# T2BasicSerialSplitterRevC.net
KiCad netlist of a schematic drawn in EAGLE
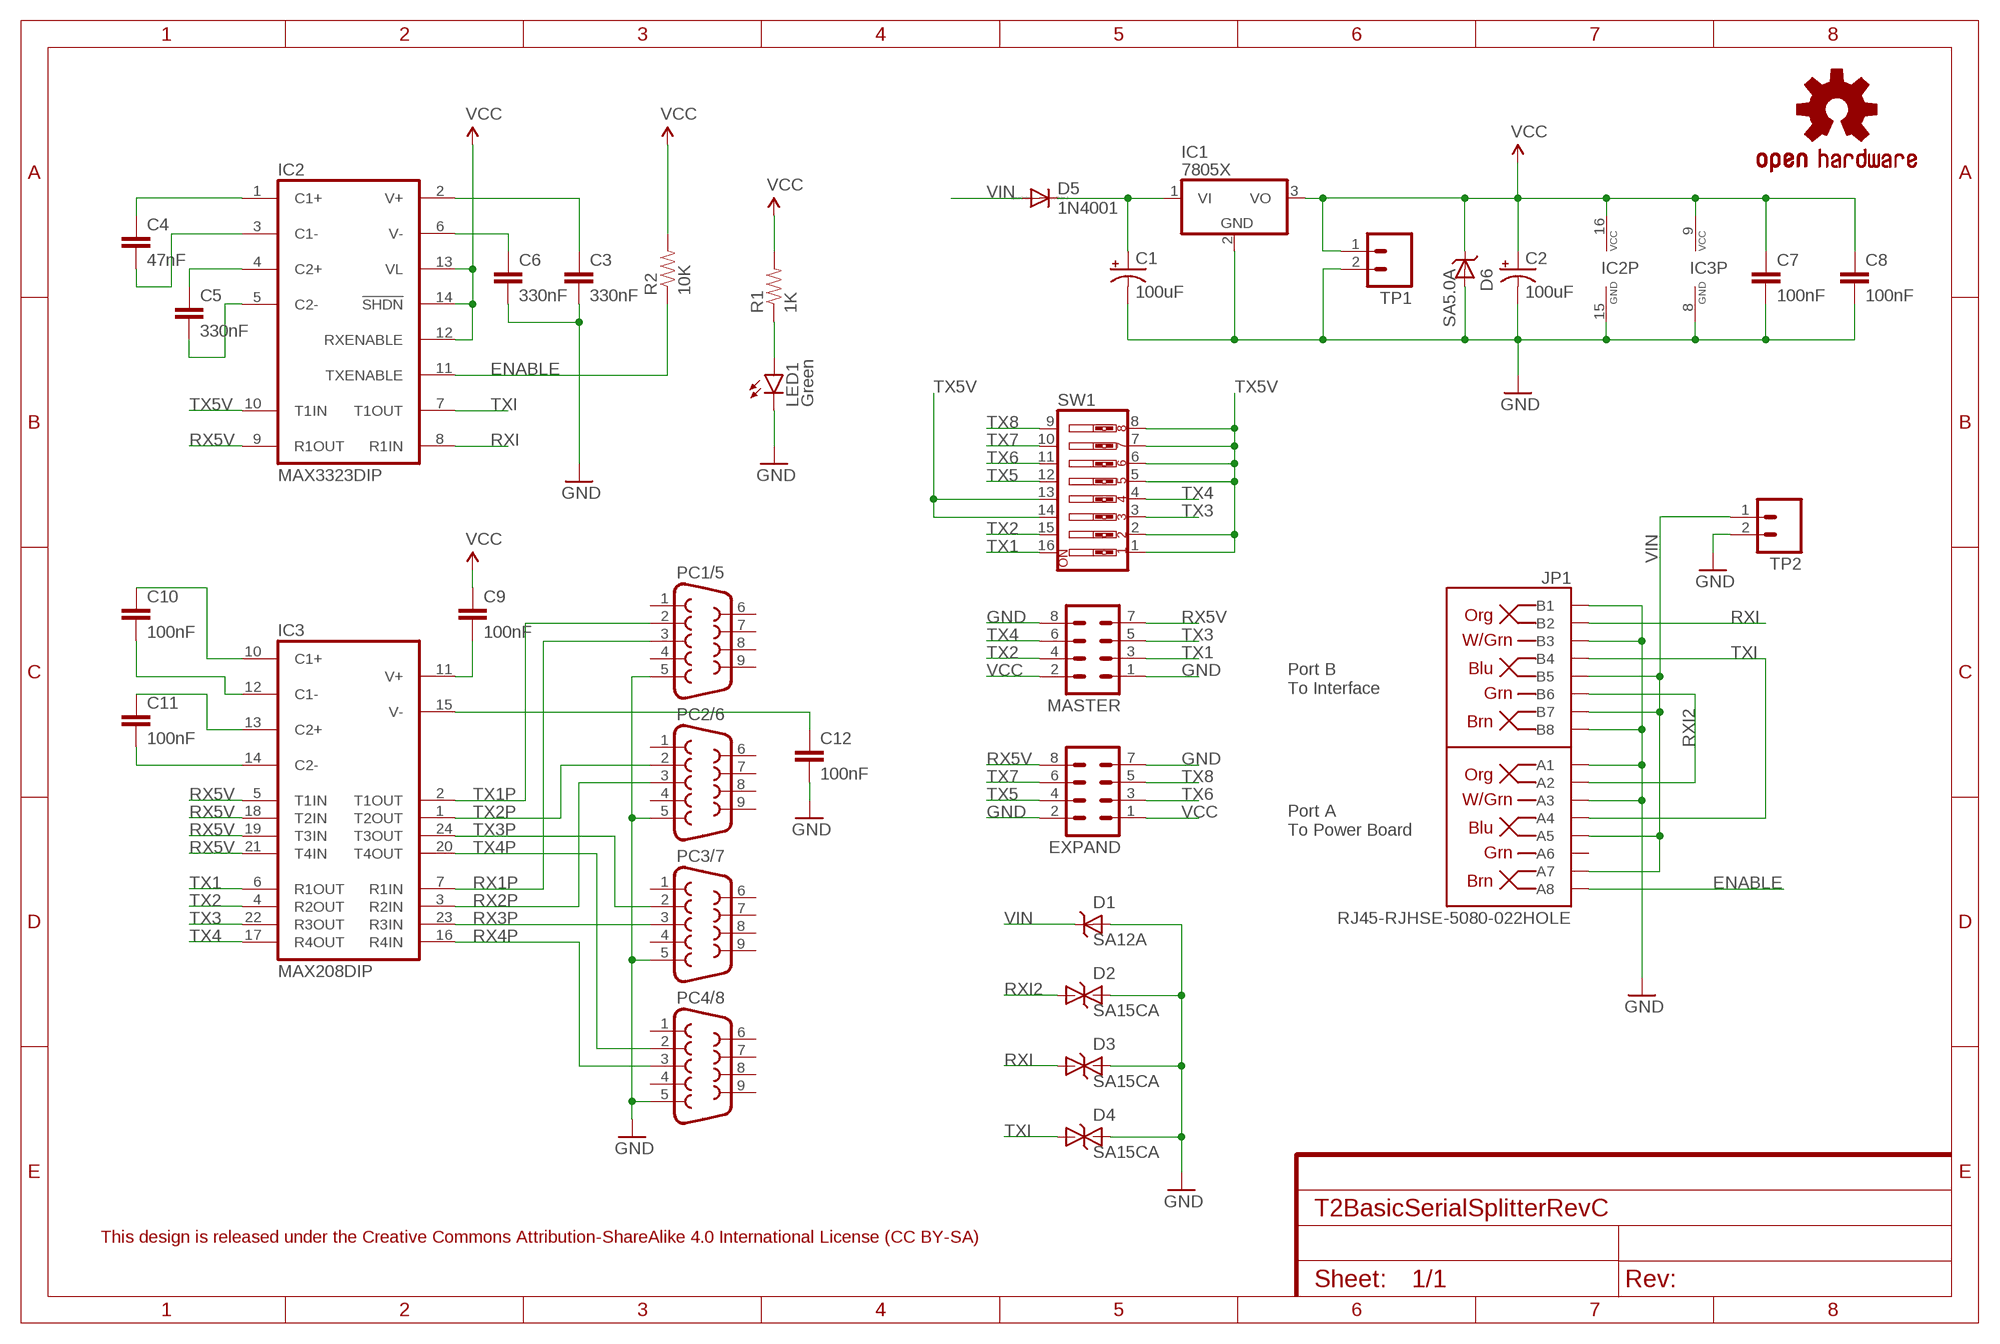
[diagram p0: schematic, sheet 1]

(export (version "E")
  (design (tool "Eeschema 10.0.6"))
  (components
    (comp (ref "C1")
      (value "100uF")
      (footprint "eagle-import:CPOL-RADIAL-100UF-25V")
      (libsource (lib "eagle-import") (part "CAP_POLPTH1"))
    )
    (comp (ref "C2")
      (value "100uF")
      (footprint "eagle-import:CPOL-RADIAL-100UF-25V")
      (libsource (lib "eagle-import") (part "CAP_POLPTH1"))
    )
    (comp (ref "C3")
      (value "330nF")
      (footprint "eagle-import:CAP-PTH-SMALL")
      (libsource (lib "eagle-import") (part "CAPPTH"))
    )
    (comp (ref "C4")
      (value "47nF")
      (footprint "eagle-import:CAP-PTH-SMALL")
      (libsource (lib "eagle-import") (part "CAPPTH"))
    )
    (comp (ref "C5")
      (value "330nF")
      (footprint "eagle-import:CAP-PTH-SMALL")
      (libsource (lib "eagle-import") (part "CAPPTH"))
    )
    (comp (ref "C6")
      (value "330nF")
      (footprint "eagle-import:CAP-PTH-SMALL")
      (libsource (lib "eagle-import") (part "CAPPTH"))
    )
    (comp (ref "C7")
      (value "100nF")
      (footprint "eagle-import:CAP-PTH-SMALL")
      (libsource (lib "eagle-import") (part "CAPPTH"))
    )
    (comp (ref "C8")
      (value "100nF")
      (footprint "eagle-import:CAP-PTH-SMALL")
      (libsource (lib "eagle-import") (part "CAPPTH"))
    )
    (comp (ref "C9")
      (value "100nF")
      (footprint "eagle-import:CAP-PTH-SMALL")
      (libsource (lib "eagle-import") (part "CAPPTH"))
    )
    (comp (ref "C10")
      (value "100nF")
      (footprint "eagle-import:CAP-PTH-SMALL")
      (libsource (lib "eagle-import") (part "CAPPTH"))
    )
    (comp (ref "C11")
      (value "100nF")
      (footprint "eagle-import:CAP-PTH-SMALL")
      (libsource (lib "eagle-import") (part "CAPPTH"))
    )
    (comp (ref "C12")
      (value "100nF")
      (footprint "eagle-import:CAP-PTH-SMALL")
      (libsource (lib "eagle-import") (part "CAPPTH"))
    )
    (comp (ref "D1")
      (value "SA12A")
      (footprint "eagle-import:DO41_TVS_UNI")
      (libsource (lib "eagle-import") (part "SA12A"))
    )
    (comp (ref "D2")
      (value "SA15CA")
      (footprint "eagle-import:DO41_TVS_BI")
      (libsource (lib "eagle-import") (part "SA15CA"))
    )
    (comp (ref "D3")
      (value "SA15CA")
      (footprint "eagle-import:DO41_TVS_BI")
      (libsource (lib "eagle-import") (part "SA15CA"))
    )
    (comp (ref "D4")
      (value "SA15CA")
      (footprint "eagle-import:DO41_TVS_BI")
      (libsource (lib "eagle-import") (part "SA15CA"))
    )
    (comp (ref "D5")
      (value "1N4001")
      (footprint "eagle-import:DO41_DIODE")
      (libsource (lib "eagle-import") (part "1N4001"))
    )
    (comp (ref "D6")
      (value "SA5.0A")
      (footprint "eagle-import:DO41_TVS_UNI")
      (libsource (lib "eagle-import") (part "SA5.0A"))
    )
    (comp (ref "EXPAND")
      (value "M04X2POL")
      (footprint "eagle-import:2X4-POLARISED")
      (libsource (lib "eagle-import") (part "M04X2POL"))
    )
    (comp (ref "IC1")
      (value "7805X")
      (footprint "eagle-import:TO220H")
      (libsource (lib "eagle-import") (part "7805X"))
    )
    (comp (ref "IC2")
      (value "MAX3323DIP")
      (footprint "eagle-import:DIL16")
      (libsource (lib "eagle-import") (part "MAX3323DIP"))
    )
    (comp (ref "IC3")
      (value "MAX208DIP")
      (footprint "eagle-import:DIL24")
      (libsource (lib "eagle-import") (part "MAX208DIP"))
    )
    (comp (ref "JP1")
      (value "RJ45-RJHSE-5080-022HOLE")
      (footprint "eagle-import:RJ45-RJHSE-5080-02")
      (libsource (lib "eagle-import") (part "RJ45-RJHSE-5080-022HOLE"))
    )
    (comp (ref "LED1")
      (value "Green")
      (footprint "eagle-import:LED3MM_LARGEHOLES")
      (libsource (lib "eagle-import") (part "LED-LH3MM"))
    )
    (comp (ref "LOGO1")
      (value "OSHW-LOGOS")
      (footprint "eagle-import:OSHW-LOGO-S")
      (libsource (lib "eagle-import") (part "OSHW-LOGOS"))
    )
    (comp (ref "MASTER")
      (value "M04X2POL")
      (footprint "eagle-import:2X4-POLARISED")
      (libsource (lib "eagle-import") (part "M04X2POL"))
    )
    (comp (ref "PC1/5")
      (value "DB9-CONNECTOR-PCBFEMALE")
      (footprint "eagle-import:MULTICOMP-DB9-FEMALE-PCB-90DEG")
      (libsource (lib "eagle-import") (part "DB9-CONNECTOR-PCBFEMALE"))
    )
    (comp (ref "PC2/6")
      (value "DB9-CONNECTOR-PCBFEMALE")
      (footprint "eagle-import:MULTICOMP-DB9-FEMALE-PCB-90DEG")
      (libsource (lib "eagle-import") (part "DB9-CONNECTOR-PCBFEMALE"))
    )
    (comp (ref "PC3/7")
      (value "DB9-CONNECTOR-PCBFEMALE")
      (footprint "eagle-import:MULTICOMP-DB9-FEMALE-PCB-90DEG")
      (libsource (lib "eagle-import") (part "DB9-CONNECTOR-PCBFEMALE"))
    )
    (comp (ref "PC4/8")
      (value "DB9-CONNECTOR-PCBFEMALE")
      (footprint "eagle-import:MULTICOMP-DB9-FEMALE-PCB-90DEG")
      (libsource (lib "eagle-import") (part "DB9-CONNECTOR-PCBFEMALE"))
    )
    (comp (ref "R1")
      (value "1K")
      (footprint "eagle-import:AXIAL-0.4")
      (libsource (lib "eagle-import") (part "RESISTORPTH-1/4W"))
    )
    (comp (ref "R2")
      (value "10K")
      (footprint "eagle-import:AXIAL-0.4")
      (libsource (lib "eagle-import") (part "RESISTORPTH-1/4W"))
    )
    (comp (ref "SW1")
      (value "SW_DIP-8")
      (footprint "eagle-import:DIPSWITCH-08")
      (libsource (lib "eagle-import") (part "SW_DIP-8"))
    )
    (comp (ref "TP1")
      (value "M02PTH")
      (footprint "eagle-import:1X02")
      (libsource (lib "eagle-import") (part "M02PTH"))
    )
    (comp (ref "TP2")
      (value "M02PTH")
      (footprint "eagle-import:1X02")
      (libsource (lib "eagle-import") (part "M02PTH"))
    )
  )
  (nets
    (net (code "1") (name "/ENABLE") (class "Default")
      (node (ref "IC2") (pin "11") (pinfunction "TXENABLE_11") (pintype "bidirectional"))
      (node (ref "JP1") (pin "A8") (pinfunction "A8_A8") (pintype "bidirectional"))
      (node (ref "R2") (pin "P$1") (pinfunction "1_P$1") (pintype "passive"))
    )
    (net (code "2") (name "/RX1P") (class "Default")
      (node (ref "IC3") (pin "7") (pinfunction "R1IN_7") (pintype "input"))
      (node (ref "PC1/5") (pin "3") (pinfunction "3_3") (pintype "passive"))
    )
    (net (code "3") (name "/RX2P") (class "Default")
      (node (ref "IC3") (pin "3") (pinfunction "R2IN_3") (pintype "input"))
      (node (ref "PC2/6") (pin "3") (pinfunction "3_3") (pintype "passive"))
    )
    (net (code "4") (name "/RX3P") (class "Default")
      (node (ref "IC3") (pin "23") (pinfunction "R3IN_23") (pintype "input"))
      (node (ref "PC3/7") (pin "3") (pinfunction "3_3") (pintype "passive"))
    )
    (net (code "5") (name "/RX4P") (class "Default")
      (node (ref "IC3") (pin "16") (pinfunction "R4IN_16") (pintype "input"))
      (node (ref "PC4/8") (pin "3") (pinfunction "3_3") (pintype "passive"))
    )
    (net (code "6") (name "/RX5V") (class "Default")
      (node (ref "EXPAND") (pin "8") (pinfunction "8_8") (pintype "passive"))
      (node (ref "IC2") (pin "9") (pinfunction "R1OUT_9") (pintype "output"))
      (node (ref "IC3") (pin "18") (pinfunction "T2IN_18") (pintype "input"))
      (node (ref "IC3") (pin "19") (pinfunction "T3IN_19") (pintype "input"))
      (node (ref "IC3") (pin "21") (pinfunction "T4IN_21") (pintype "input"))
      (node (ref "IC3") (pin "5") (pinfunction "T1IN_5") (pintype "input"))
      (node (ref "MASTER") (pin "7") (pinfunction "7_7") (pintype "passive"))
    )
    (net (code "7") (name "/RXI") (class "Default")
      (node (ref "D3") (pin "A") (pinfunction "A_A") (pintype "passive"))
      (node (ref "IC2") (pin "8") (pinfunction "R1IN_8") (pintype "input"))
      (node (ref "JP1") (pin "B2") (pinfunction "B2_B2") (pintype "bidirectional"))
    )
    (net (code "8") (name "/RXI2") (class "Default")
      (node (ref "D2") (pin "A") (pinfunction "A_A") (pintype "passive"))
      (node (ref "JP1") (pin "A2") (pinfunction "A2_A2") (pintype "bidirectional"))
      (node (ref "JP1") (pin "B6") (pinfunction "B6_B6") (pintype "bidirectional"))
    )
    (net (code "9") (name "/TX1") (class "Default")
      (node (ref "IC3") (pin "6") (pinfunction "R1OUT_6") (pintype "output"))
      (node (ref "MASTER") (pin "3") (pinfunction "3_3") (pintype "passive"))
      (node (ref "SW1") (pin "16") (pinfunction "16_16") (pintype "passive"))
    )
    (net (code "10") (name "/TX1P") (class "Default")
      (node (ref "IC3") (pin "2") (pinfunction "T1OUT_2") (pintype "output"))
      (node (ref "PC1/5") (pin "2") (pinfunction "2_2") (pintype "passive"))
    )
    (net (code "11") (name "/TX2") (class "Default")
      (node (ref "IC3") (pin "4") (pinfunction "R2OUT_4") (pintype "output"))
      (node (ref "MASTER") (pin "4") (pinfunction "4_4") (pintype "passive"))
      (node (ref "SW1") (pin "15") (pinfunction "15_15") (pintype "passive"))
    )
    (net (code "12") (name "/TX2P") (class "Default")
      (node (ref "IC3") (pin "1") (pinfunction "T2OUT_1") (pintype "output"))
      (node (ref "PC2/6") (pin "2") (pinfunction "2_2") (pintype "passive"))
    )
    (net (code "13") (name "/TX3") (class "Default")
      (node (ref "IC3") (pin "22") (pinfunction "R3OUT_22") (pintype "output"))
      (node (ref "MASTER") (pin "5") (pinfunction "5_5") (pintype "passive"))
      (node (ref "SW1") (pin "3") (pinfunction "3_3") (pintype "passive"))
    )
    (net (code "14") (name "/TX3P") (class "Default")
      (node (ref "IC3") (pin "24") (pinfunction "T3OUT_24") (pintype "output"))
      (node (ref "PC3/7") (pin "2") (pinfunction "2_2") (pintype "passive"))
    )
    (net (code "15") (name "/TX4") (class "Default")
      (node (ref "IC3") (pin "17") (pinfunction "R4OUT_17") (pintype "output"))
      (node (ref "MASTER") (pin "6") (pinfunction "6_6") (pintype "passive"))
      (node (ref "SW1") (pin "4") (pinfunction "4_4") (pintype "passive"))
    )
    (net (code "16") (name "/TX4P") (class "Default")
      (node (ref "IC3") (pin "20") (pinfunction "T4OUT_20") (pintype "output"))
      (node (ref "PC4/8") (pin "2") (pinfunction "2_2") (pintype "passive"))
    )
    (net (code "17") (name "/TX5") (class "Default")
      (node (ref "EXPAND") (pin "4") (pinfunction "4_4") (pintype "passive"))
      (node (ref "SW1") (pin "12") (pinfunction "12_12") (pintype "passive"))
    )
    (net (code "18") (name "/TX5V") (class "Default")
      (node (ref "IC2") (pin "10") (pinfunction "T1IN_10") (pintype "input"))
      (node (ref "SW1") (pin "1") (pinfunction "1_1") (pintype "passive"))
      (node (ref "SW1") (pin "13") (pinfunction "13_13") (pintype "passive"))
      (node (ref "SW1") (pin "14") (pinfunction "14_14") (pintype "passive"))
      (node (ref "SW1") (pin "2") (pinfunction "2_2") (pintype "passive"))
      (node (ref "SW1") (pin "5") (pinfunction "5_5") (pintype "passive"))
      (node (ref "SW1") (pin "6") (pinfunction "6_6") (pintype "passive"))
      (node (ref "SW1") (pin "7") (pinfunction "7_7") (pintype "passive"))
      (node (ref "SW1") (pin "8") (pinfunction "8_8") (pintype "passive"))
    )
    (net (code "19") (name "/TX6") (class "Default")
      (node (ref "EXPAND") (pin "3") (pinfunction "3_3") (pintype "passive"))
      (node (ref "SW1") (pin "11") (pinfunction "11_11") (pintype "passive"))
    )
    (net (code "20") (name "/TX7") (class "Default")
      (node (ref "EXPAND") (pin "6") (pinfunction "6_6") (pintype "passive"))
      (node (ref "SW1") (pin "10") (pinfunction "10_10") (pintype "passive"))
    )
    (net (code "21") (name "/TX8") (class "Default")
      (node (ref "EXPAND") (pin "5") (pinfunction "5_5") (pintype "passive"))
      (node (ref "SW1") (pin "9") (pinfunction "9_9") (pintype "passive"))
    )
    (net (code "22") (name "/TXI") (class "Default")
      (node (ref "D4") (pin "A") (pinfunction "A_A") (pintype "passive"))
      (node (ref "IC2") (pin "7") (pinfunction "T1OUT_7") (pintype "output"))
      (node (ref "JP1") (pin "A4") (pinfunction "A4_A4") (pintype "bidirectional"))
      (node (ref "JP1") (pin "B4") (pinfunction "B4_B4") (pintype "bidirectional"))
    )
    (net (code "23") (name "/VIN") (class "Default")
      (node (ref "D1") (pin "CATHODE") (pinfunction "CATHODE_CATHODE") (pintype "passive"))
      (node (ref "D5") (pin "A") (pinfunction "A_A") (pintype "passive"))
      (node (ref "JP1") (pin "A5") (pinfunction "A5_A5") (pintype "bidirectional"))
      (node (ref "JP1") (pin "A7") (pinfunction "A7_A7") (pintype "bidirectional"))
      (node (ref "JP1") (pin "B5") (pinfunction "B5_B5") (pintype "bidirectional"))
      (node (ref "JP1") (pin "B7") (pinfunction "B7_B7") (pintype "bidirectional"))
      (node (ref "TP2") (pin "1") (pinfunction "1_1") (pintype "passive"))
    )
    (net (code "24") (name "GND") (class "Default")
      (node (ref "C1") (pin "2") (pinfunction "-_2") (pintype "passive"))
      (node (ref "C12") (pin "2") (pinfunction "2_2") (pintype "passive"))
      (node (ref "C2") (pin "2") (pinfunction "-_2") (pintype "passive"))
      (node (ref "C3") (pin "2") (pinfunction "2_2") (pintype "passive"))
      (node (ref "C6") (pin "2") (pinfunction "2_2") (pintype "passive"))
      (node (ref "C7") (pin "2") (pinfunction "2_2") (pintype "passive"))
      (node (ref "C8") (pin "2") (pinfunction "2_2") (pintype "passive"))
      (node (ref "D1") (pin "ANODE") (pinfunction "ANODE_ANODE") (pintype "passive"))
      (node (ref "D2") (pin "C") (pinfunction "C_C") (pintype "passive"))
      (node (ref "D3") (pin "C") (pinfunction "C_C") (pintype "passive"))
      (node (ref "D4") (pin "C") (pinfunction "C_C") (pintype "passive"))
      (node (ref "D6") (pin "ANODE") (pinfunction "ANODE_ANODE") (pintype "passive"))
      (node (ref "EXPAND") (pin "2") (pinfunction "2_2") (pintype "passive"))
      (node (ref "EXPAND") (pin "7") (pinfunction "7_7") (pintype "passive"))
      (node (ref "IC1") (pin "2") (pinfunction "GND_2") (pintype "passive"))
      (node (ref "IC2") (pin "15") (pinfunction "GND_15") (pintype "power_in"))
      (node (ref "IC3") (pin "8") (pinfunction "GND_8") (pintype "power_in"))
      (node (ref "JP1") (pin "A1") (pinfunction "A1_A1") (pintype "bidirectional"))
      (node (ref "JP1") (pin "A3") (pinfunction "A3_A3") (pintype "bidirectional"))
      (node (ref "JP1") (pin "B1") (pinfunction "B1_B1") (pintype "bidirectional"))
      (node (ref "JP1") (pin "B3") (pinfunction "B3_B3") (pintype "bidirectional"))
      (node (ref "JP1") (pin "B8") (pinfunction "B8_B8") (pintype "bidirectional"))
      (node (ref "LED1") (pin "K") (pinfunction "C_K") (pintype "passive"))
      (node (ref "MASTER") (pin "1") (pinfunction "1_1") (pintype "passive"))
      (node (ref "MASTER") (pin "8") (pinfunction "8_8") (pintype "passive"))
      (node (ref "PC1/5") (pin "5") (pinfunction "5_5") (pintype "passive"))
      (node (ref "PC2/6") (pin "5") (pinfunction "5_5") (pintype "passive"))
      (node (ref "PC3/7") (pin "5") (pinfunction "5_5") (pintype "passive"))
      (node (ref "PC4/8") (pin "5") (pinfunction "5_5") (pintype "passive"))
      (node (ref "TP1") (pin "2") (pinfunction "2_2") (pintype "passive"))
      (node (ref "TP2") (pin "2") (pinfunction "2_2") (pintype "passive"))
    )
    (net (code "25") (name "Net-(C1-+)") (class "Default")
      (node (ref "C1") (pin "1") (pinfunction "+_1") (pintype "passive"))
      (node (ref "D5") (pin "C") (pinfunction "C_C") (pintype "passive"))
      (node (ref "IC1") (pin "1") (pinfunction "VI_1") (pintype "input"))
    )
    (net (code "26") (name "Net-(IC2A-C1+)") (class "Default")
      (node (ref "C4") (pin "1") (pinfunction "1_1") (pintype "passive"))
      (node (ref "IC2") (pin "1") (pinfunction "C1+_1") (pintype "bidirectional"))
    )
    (net (code "27") (name "Net-(IC2A-C1-)") (class "Default")
      (node (ref "C4") (pin "2") (pinfunction "2_2") (pintype "passive"))
      (node (ref "IC2") (pin "3") (pinfunction "C1-_3") (pintype "bidirectional"))
    )
    (net (code "28") (name "Net-(IC2A-C2+)") (class "Default")
      (node (ref "C5") (pin "1") (pinfunction "1_1") (pintype "passive"))
      (node (ref "IC2") (pin "4") (pinfunction "C2+_4") (pintype "bidirectional"))
    )
    (net (code "29") (name "Net-(IC2A-C2-)") (class "Default")
      (node (ref "C5") (pin "2") (pinfunction "2_2") (pintype "passive"))
      (node (ref "IC2") (pin "5") (pinfunction "C2-_5") (pintype "bidirectional"))
    )
    (net (code "30") (name "Net-(IC2A-V+)") (class "Default")
      (node (ref "C3") (pin "1") (pinfunction "1_1") (pintype "passive"))
      (node (ref "IC2") (pin "2") (pinfunction "V+_2") (pintype "bidirectional"))
    )
    (net (code "31") (name "Net-(IC2A-V-)") (class "Default")
      (node (ref "C6") (pin "1") (pinfunction "1_1") (pintype "passive"))
      (node (ref "IC2") (pin "6") (pinfunction "V-_6") (pintype "bidirectional"))
    )
    (net (code "32") (name "Net-(IC3A-C1+)") (class "Default")
      (node (ref "C10") (pin "1") (pinfunction "1_1") (pintype "passive"))
      (node (ref "IC3") (pin "10") (pinfunction "C1+_10") (pintype "bidirectional"))
    )
    (net (code "33") (name "Net-(IC3A-C1-)") (class "Default")
      (node (ref "C10") (pin "2") (pinfunction "2_2") (pintype "passive"))
      (node (ref "IC3") (pin "12") (pinfunction "C1-_12") (pintype "bidirectional"))
    )
    (net (code "34") (name "Net-(IC3A-C2+)") (class "Default")
      (node (ref "C11") (pin "1") (pinfunction "1_1") (pintype "passive"))
      (node (ref "IC3") (pin "13") (pinfunction "C2+_13") (pintype "bidirectional"))
    )
    (net (code "35") (name "Net-(IC3A-C2-)") (class "Default")
      (node (ref "C11") (pin "2") (pinfunction "2_2") (pintype "passive"))
      (node (ref "IC3") (pin "14") (pinfunction "C2-_14") (pintype "bidirectional"))
    )
    (net (code "36") (name "Net-(IC3A-V+)") (class "Default")
      (node (ref "C9") (pin "2") (pinfunction "2_2") (pintype "passive"))
      (node (ref "IC3") (pin "11") (pinfunction "V+_11") (pintype "bidirectional"))
    )
    (net (code "37") (name "Net-(IC3A-V-)") (class "Default")
      (node (ref "C12") (pin "1") (pinfunction "1_1") (pintype "passive"))
      (node (ref "IC3") (pin "15") (pinfunction "V-_15") (pintype "bidirectional"))
    )
    (net (code "38") (name "Net-(R1-1)") (class "Default")
      (node (ref "LED1") (pin "A") (pinfunction "A_A") (pintype "passive"))
      (node (ref "R1") (pin "P$1") (pinfunction "1_P$1") (pintype "passive"))
    )
    (net (code "39") (name "VCC") (class "Default")
      (node (ref "C2") (pin "1") (pinfunction "+_1") (pintype "passive"))
      (node (ref "C7") (pin "1") (pinfunction "1_1") (pintype "passive"))
      (node (ref "C8") (pin "1") (pinfunction "1_1") (pintype "passive"))
      (node (ref "C9") (pin "1") (pinfunction "1_1") (pintype "passive"))
      (node (ref "D6") (pin "CATHODE") (pinfunction "CATHODE_CATHODE") (pintype "passive"))
      (node (ref "EXPAND") (pin "1") (pinfunction "1_1") (pintype "passive"))
      (node (ref "IC1") (pin "3") (pinfunction "VO_3") (pintype "passive"))
      (node (ref "IC2") (pin "12") (pinfunction "RXENABLE_12") (pintype "bidirectional"))
      (node (ref "IC2") (pin "13") (pinfunction "VL_13") (pintype "bidirectional"))
      (node (ref "IC2") (pin "14") (pinfunction "~{SHDN}_14") (pintype "bidirectional"))
      (node (ref "IC2") (pin "16") (pinfunction "VCC_16") (pintype "power_in"))
      (node (ref "IC3") (pin "9") (pinfunction "VCC_9") (pintype "power_in"))
      (node (ref "MASTER") (pin "2") (pinfunction "2_2") (pintype "passive"))
      (node (ref "R1") (pin "P$2") (pinfunction "2_P$2") (pintype "passive"))
      (node (ref "R2") (pin "P$2") (pinfunction "2_P$2") (pintype "passive"))
      (node (ref "TP1") (pin "1") (pinfunction "1_1") (pintype "passive"))
    )
    (net (code "40") (name "unconnected-(JP1-PadA6)") (class "Default")
      (node (ref "JP1") (pin "A6") (pinfunction "A6_A6") (pintype "bidirectional"))
    )
    (net (code "41") (name "unconnected-(PC1/5-Pad1)") (class "Default")
      (node (ref "PC1/5") (pin "1") (pinfunction "1_1") (pintype "passive"))
    )
    (net (code "42") (name "unconnected-(PC1/5-Pad4)") (class "Default")
      (node (ref "PC1/5") (pin "4") (pinfunction "4_4") (pintype "passive"))
    )
    (net (code "43") (name "unconnected-(PC1/5-Pad6)") (class "Default")
      (node (ref "PC1/5") (pin "6") (pinfunction "6_6") (pintype "passive"))
    )
    (net (code "44") (name "unconnected-(PC1/5-Pad7)") (class "Default")
      (node (ref "PC1/5") (pin "7") (pinfunction "7_7") (pintype "passive"))
    )
    (net (code "45") (name "unconnected-(PC1/5-Pad8)") (class "Default")
      (node (ref "PC1/5") (pin "8") (pinfunction "8_8") (pintype "passive"))
    )
    (net (code "46") (name "unconnected-(PC1/5-Pad9)") (class "Default")
      (node (ref "PC1/5") (pin "9") (pinfunction "9_9") (pintype "passive"))
    )
    (net (code "47") (name "unconnected-(PC2/6-Pad1)") (class "Default")
      (node (ref "PC2/6") (pin "1") (pinfunction "1_1") (pintype "passive"))
    )
    (net (code "48") (name "unconnected-(PC2/6-Pad4)") (class "Default")
      (node (ref "PC2/6") (pin "4") (pinfunction "4_4") (pintype "passive"))
    )
    (net (code "49") (name "unconnected-(PC2/6-Pad6)") (class "Default")
      (node (ref "PC2/6") (pin "6") (pinfunction "6_6") (pintype "passive"))
    )
    (net (code "50") (name "unconnected-(PC2/6-Pad7)") (class "Default")
      (node (ref "PC2/6") (pin "7") (pinfunction "7_7") (pintype "passive"))
    )
    (net (code "51") (name "unconnected-(PC2/6-Pad8)") (class "Default")
      (node (ref "PC2/6") (pin "8") (pinfunction "8_8") (pintype "passive"))
    )
    (net (code "52") (name "unconnected-(PC2/6-Pad9)") (class "Default")
      (node (ref "PC2/6") (pin "9") (pinfunction "9_9") (pintype "passive"))
    )
    (net (code "53") (name "unconnected-(PC3/7-Pad1)") (class "Default")
      (node (ref "PC3/7") (pin "1") (pinfunction "1_1") (pintype "passive"))
    )
    (net (code "54") (name "unconnected-(PC3/7-Pad4)") (class "Default")
      (node (ref "PC3/7") (pin "4") (pinfunction "4_4") (pintype "passive"))
    )
    (net (code "55") (name "unconnected-(PC3/7-Pad6)") (class "Default")
      (node (ref "PC3/7") (pin "6") (pinfunction "6_6") (pintype "passive"))
    )
    (net (code "56") (name "unconnected-(PC3/7-Pad7)") (class "Default")
      (node (ref "PC3/7") (pin "7") (pinfunction "7_7") (pintype "passive"))
    )
    (net (code "57") (name "unconnected-(PC3/7-Pad8)") (class "Default")
      (node (ref "PC3/7") (pin "8") (pinfunction "8_8") (pintype "passive"))
    )
    (net (code "58") (name "unconnected-(PC3/7-Pad9)") (class "Default")
      (node (ref "PC3/7") (pin "9") (pinfunction "9_9") (pintype "passive"))
    )
    (net (code "59") (name "unconnected-(PC4/8-Pad1)") (class "Default")
      (node (ref "PC4/8") (pin "1") (pinfunction "1_1") (pintype "passive"))
    )
    (net (code "60") (name "unconnected-(PC4/8-Pad4)") (class "Default")
      (node (ref "PC4/8") (pin "4") (pinfunction "4_4") (pintype "passive"))
    )
    (net (code "61") (name "unconnected-(PC4/8-Pad6)") (class "Default")
      (node (ref "PC4/8") (pin "6") (pinfunction "6_6") (pintype "passive"))
    )
    (net (code "62") (name "unconnected-(PC4/8-Pad7)") (class "Default")
      (node (ref "PC4/8") (pin "7") (pinfunction "7_7") (pintype "passive"))
    )
    (net (code "63") (name "unconnected-(PC4/8-Pad8)") (class "Default")
      (node (ref "PC4/8") (pin "8") (pinfunction "8_8") (pintype "passive"))
    )
    (net (code "64") (name "unconnected-(PC4/8-Pad9)") (class "Default")
      (node (ref "PC4/8") (pin "9") (pinfunction "9_9") (pintype "passive"))
    )
  )
)
